# can.net
KiCad netlist of a schematic drawn in Altium Designer
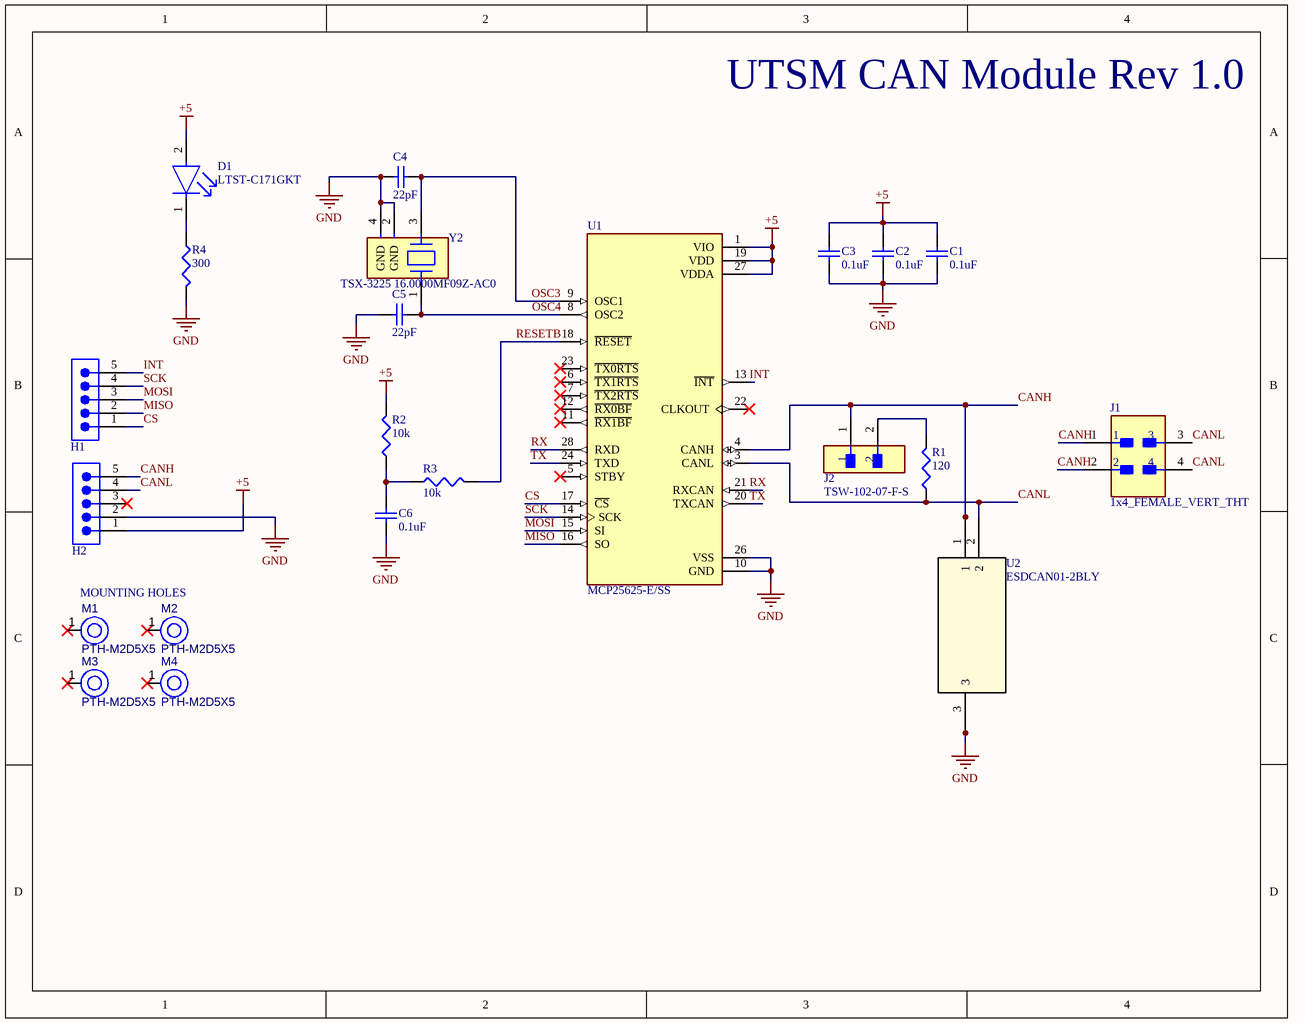
[diagram p0: can.SchDoc]

(export (version "E")
  (design (tool "Eeschema 10.0.6"))
  (components
    (comp (ref "C1")
      (value "0.1uF")
      (footprint "0603c")
      (description "0603 Capacitor")
      (fields (field (name "Comment") "Cap") (field (name "PUBLISHER") "Altium Limited"))
      (libsource (lib "Peripheral") (part "Cap"))
    )
    (comp (ref "C2")
      (value "0.1uF")
      (footprint "0603c")
      (description "SMD Capacitor")
      (fields (field (name "Comment") "Cap") (field (name "PUBLISHER") "Altium Limited"))
      (libsource (lib "can") (part "Cap"))
    )
    (comp (ref "C3")
      (value "0.1uF")
      (footprint "0603c")
      (description "SMD Capacitor")
      (fields (field (name "Comment") "Cap") (field (name "PUBLISHER") "Altium Limited"))
      (libsource (lib "can") (part "Cap"))
    )
    (comp (ref "C4")
      (value "22pF")
      (footprint "0603c")
      (description "0603 Capacitor")
      (fields (field (name "PUBLISHER") "Altium Limited"))
      (libsource (lib "can") (part "Cap"))
    )
    (comp (ref "C5")
      (value "22pF")
      (footprint "0603c")
      (description "SMD Capacitor")
      (fields (field (name "Comment") "Cap") (field (name "PUBLISHER") "Altium Limited"))
      (libsource (lib "can") (part "Cap"))
    )
    (comp (ref "C6")
      (value "0.1uF")
      (footprint "0603c")
      (description "SMD Capacitor")
      (fields (field (name "Comment") "Cap") (field (name "PUBLISHER") "Altium Limited"))
      (libsource (lib "can") (part "Cap"))
    )
    (comp (ref "D1")
      (value "LTST-C171GKT")
      (footprint "FP-LTST-C171GKT-MFG")
      (description "LED GREEN CLEAR CHIP SMD")
      (libsource (lib "Altium Content Vault") (part "8706943c75ba83719d021d2fdc84c58"))
    )
    (comp (ref "H1")
      (value "61300511121")
      (footprint "can:61300511121")
      (description "WR-PHD Pin Header, THT, Vertical, pitch 2.54mm, 1 Row, 5P")
      (fields (field (name "MANUFACTURER") "Wurth Elektronik"))
      (libsource (lib "can") (part "61300511121"))
    )
    (comp (ref "H2")
      (value "61300511121")
      (footprint "61300511121")
      (description "WR-PHD Pin Header, THT, Vertical, pitch 2.54mm, 1 Row, 5P")
      (fields (field (name "MANUFACTURER") "Wurth Elektronik"))
      (libsource (lib "can") (part "61300511121"))
    )
    (comp (ref "J1")
      (value "1x4_FEMALE_VERT_THT")
      (footprint "FP-0039281043-MFG")
      (description "CONN HEADER VERT 4POS 4.2MM. 0039281043")
      (fields (field (name "MANUFACTURER PART NUMBER") "0039281043") (field (name "MANUFACTURER") "Molex"))
      (libsource (lib "can") (part "1x4_FEMALE_POWER"))
    )
    (comp (ref "J2")
      (value "TSW-102-07-F-S")
      (footprint "FP-TSW-102-07-F-S-MFG")
      (description "CONN HEADER VERT 2POS 2.54MM")
      (libsource (lib "Altium Content Vault") (part "3bc925449376181038e59eaffc5286c"))
    )
    (comp (ref "M1")
      (value "PTH-M2D5X5")
      (footprint "PTH-M2D5X5")
      (description "M2 PTH (2.5mm), 5mm pad")
      (libsource (lib "can") (part "PTH-M2D5X5"))
    )
    (comp (ref "M2")
      (value "PTH-M2D5X5")
      (footprint "PTH-M2D5X5")
      (description "M2 PTH (2.5mm), 5mm pad")
      (libsource (lib "can") (part "PTH-M2D5X5"))
    )
    (comp (ref "M3")
      (value "PTH-M2D5X5")
      (footprint "PTH-M2D5X5")
      (description "M2 PTH (2.5mm), 5mm pad")
      (libsource (lib "can") (part "PTH-M2D5X5"))
    )
    (comp (ref "M4")
      (value "PTH-M2D5X5")
      (footprint "PTH-M2D5X5")
      (description "M2 PTH (2.5mm), 5mm pad")
      (libsource (lib "can") (part "PTH-M2D5X5"))
    )
    (comp (ref "R1")
      (value "120")
      (footprint "0603r")
      (description "SMD Resistor")
      (fields (field (name "Comment") "Res3") (field (name "PUBLISHER") "Altium Limited"))
      (libsource (lib "can") (part "Res3"))
    )
    (comp (ref "R2")
      (value "10k")
      (footprint "0603r")
      (description "SMD Resistor")
      (fields (field (name "Comment") "Res3") (field (name "PUBLISHER") "Altium Limited"))
      (libsource (lib "can") (part "Res3"))
    )
    (comp (ref "R3")
      (value "10k")
      (footprint "0603r")
      (description "SMD Resistor")
      (fields (field (name "Comment") "Res3") (field (name "PUBLISHER") "Altium Limited"))
      (libsource (lib "can") (part "Res3"))
    )
    (comp (ref "R4")
      (value "300")
      (footprint "0603r")
      (description "SMD Resistor")
      (fields (field (name "Comment") "Res3") (field (name "PUBLISHER") "Altium Limited"))
      (libsource (lib "can") (part "Res3"))
    )
    (comp (ref "U1")
      (value "MCP25625-E/SS")
      (footprint "SOP65P780X200-28N")
      (description "1/1 Transceiver CANbus 28-SSOP")
      (fields (field (name "MF") "Microchip"))
      (libsource (lib "can") (part "MCP25625-E/SS"))
    )
    (comp (ref "U2")
      (value "ESDCAN01-2BLY")
      (footprint "SOT_01-2BLY_STM")
      (fields (field (name "COPYRIGHT") "Copyright (C) 2023 Ultra Librarian. All rights reserved."))
      (libsource (lib "can") (part "ESDCAN01-2BLY"))
    )
    (comp (ref "Y2")
      (value "TSX-3225 16.0000MF09Z-AC0")
      (footprint "FP-TSX-3225-MFG")
      (description "CRYSTAL 16.0000MHZ 9PF SMD")
      (fields (field (name "TOLERANCE") "10ppm"))
      (libsource (lib "Altium Content Vault") (part "41079aabb0e87794b56622915be14ed"))
    )
  )
  (nets
    (net (code "1") (name "+5") (class "Default")
      (node (ref "C1") (pin "2") (pinfunction "2_2") (pintype "passive"))
      (node (ref "C2") (pin "2") (pinfunction "2_2") (pintype "passive"))
      (node (ref "C3") (pin "2") (pinfunction "2_2") (pintype "passive"))
      (node (ref "D1") (pin "2") (pinfunction "A_2") (pintype "passive"))
      (node (ref "H2") (pin "1") (pinfunction "1_1") (pintype "passive"))
      (node (ref "R2") (pin "2") (pinfunction "2_2") (pintype "passive"))
      (node (ref "U1") (pin "1") (pinfunction "VIO_1") (pintype "power_in"))
      (node (ref "U1") (pin "19") (pinfunction "VDD_19") (pintype "power_in"))
      (node (ref "U1") (pin "27") (pinfunction "VDDA_27") (pintype "power_in"))
    )
    (net (code "3") (name "/CANH") (class "Default")
      (node (ref "H2") (pin "5") (pinfunction "5_5") (pintype "passive"))
      (node (ref "J1") (pin "1") (pinfunction "1_1") (pintype "passive"))
      (node (ref "J1") (pin "2") (pinfunction "2_2") (pintype "passive"))
      (node (ref "J2") (pin "1") (pinfunction "1_1") (pintype "passive"))
      (node (ref "U1") (pin "4") (pinfunction "CANH_4") (pintype "bidirectional"))
      (node (ref "U2") (pin "1") (pinfunction "1_1") (pintype "passive"))
    )
    (net (code "4") (name "/CANL") (class "Default")
      (node (ref "H2") (pin "4") (pinfunction "4_4") (pintype "passive"))
      (node (ref "J1") (pin "3") (pinfunction "3_3") (pintype "passive"))
      (node (ref "J1") (pin "4") (pinfunction "4_4") (pintype "passive"))
      (node (ref "R1") (pin "1") (pinfunction "1_1") (pintype "passive"))
      (node (ref "U1") (pin "3") (pinfunction "CANL_3") (pintype "bidirectional"))
      (node (ref "U2") (pin "2") (pinfunction "2_2") (pintype "passive"))
    )
    (net (code "5") (name "/CS") (class "Default")
      (node (ref "H1") (pin "1") (pinfunction "1_1") (pintype "passive"))
      (node (ref "U1") (pin "17") (pinfunction "~{CS}_17") (pintype "input"))
    )
    (net (code "6") (name "/INT") (class "Default")
      (node (ref "H1") (pin "5") (pinfunction "5_5") (pintype "passive"))
      (node (ref "U1") (pin "13") (pinfunction "~{INT}_13") (pintype "output"))
    )
    (net (code "7") (name "/MISO") (class "Default")
      (node (ref "H1") (pin "2") (pinfunction "2_2") (pintype "passive"))
      (node (ref "U1") (pin "16") (pinfunction "SO_16") (pintype "output"))
    )
    (net (code "8") (name "/MOSI") (class "Default")
      (node (ref "H1") (pin "3") (pinfunction "3_3") (pintype "passive"))
      (node (ref "U1") (pin "15") (pinfunction "SI_15") (pintype "input"))
    )
    (net (code "9") (name "/OSC3") (class "Default")
      (node (ref "C4") (pin "2") (pinfunction "2_2") (pintype "passive"))
      (node (ref "U1") (pin "9") (pinfunction "OSC1_9") (pintype "input"))
      (node (ref "Y2") (pin "3") (pinfunction "3_3") (pintype "passive"))
    )
    (net (code "10") (name "/OSC4") (class "Default")
      (node (ref "C5") (pin "2") (pinfunction "2_2") (pintype "passive"))
      (node (ref "U1") (pin "8") (pinfunction "OSC2_8") (pintype "output"))
      (node (ref "Y2") (pin "1") (pinfunction "1_1") (pintype "passive"))
    )
    (net (code "11") (name "/RESETB") (class "Default")
      (node (ref "R3") (pin "2") (pinfunction "2_2") (pintype "passive"))
      (node (ref "U1") (pin "18") (pinfunction "~{RESET}_18") (pintype "input"))
    )
    (net (code "12") (name "/RX") (class "Default")
      (node (ref "U1") (pin "21") (pinfunction "RXCAN_21") (pintype "input"))
      (node (ref "U1") (pin "28") (pinfunction "RXD_28") (pintype "output"))
    )
    (net (code "13") (name "/SCK") (class "Default")
      (node (ref "H1") (pin "4") (pinfunction "4_4") (pintype "passive"))
      (node (ref "U1") (pin "14") (pinfunction "SCK_14") (pintype "input"))
    )
    (net (code "14") (name "/TX") (class "Default")
      (node (ref "U1") (pin "20") (pinfunction "TXCAN_20") (pintype "output"))
      (node (ref "U1") (pin "24") (pinfunction "TXD_24") (pintype "input"))
    )
    (net (code "15") (name "GND") (class "Default")
      (node (ref "C1") (pin "1") (pinfunction "1_1") (pintype "passive"))
      (node (ref "C2") (pin "1") (pinfunction "1_1") (pintype "passive"))
      (node (ref "C3") (pin "1") (pinfunction "1_1") (pintype "passive"))
      (node (ref "C4") (pin "1") (pinfunction "1_1") (pintype "passive"))
      (node (ref "C5") (pin "1") (pinfunction "1_1") (pintype "passive"))
      (node (ref "C6") (pin "1") (pinfunction "1_1") (pintype "passive"))
      (node (ref "H2") (pin "2") (pinfunction "2_2") (pintype "passive"))
      (node (ref "R4") (pin "2") (pinfunction "2_2") (pintype "passive"))
      (node (ref "U1") (pin "10") (pinfunction "GND_10") (pintype "power_in"))
      (node (ref "U1") (pin "26") (pinfunction "VSS_26") (pintype "power_in"))
      (node (ref "U2") (pin "3") (pinfunction "3_3") (pintype "passive"))
      (node (ref "Y2") (pin "2") (pinfunction "GND_2") (pintype "power_in"))
      (node (ref "Y2") (pin "4") (pinfunction "GND_4") (pintype "power_in"))
    )
    (net (code "16") (name "Net-(C6-Pad2)") (class "Default")
      (node (ref "C6") (pin "2") (pinfunction "2_2") (pintype "passive"))
      (node (ref "R2") (pin "1") (pinfunction "1_1") (pintype "passive"))
      (node (ref "R3") (pin "1") (pinfunction "1_1") (pintype "passive"))
    )
    (net (code "17") (name "Net-(D1-C)") (class "Default")
      (node (ref "D1") (pin "1") (pinfunction "C_1") (pintype "passive"))
      (node (ref "R4") (pin "1") (pinfunction "1_1") (pintype "passive"))
    )
    (net (code "18") (name "Net-(J2-Pad2)") (class "Default")
      (node (ref "J2") (pin "2") (pinfunction "2_2") (pintype "passive"))
      (node (ref "R1") (pin "2") (pinfunction "2_2") (pintype "passive"))
    )
    (net (code "19") (name "unconnected-(H2-Pad3)") (class "Default")
      (node (ref "H2") (pin "3") (pinfunction "3_3") (pintype "passive+no_connect"))
    )
    (net (code "20") (name "unconnected-(M1-H1-Pad1)") (class "Default")
      (node (ref "M1") (pin "1") (pinfunction "H1_1") (pintype "passive+no_connect"))
    )
    (net (code "21") (name "unconnected-(M2-H1-Pad1)") (class "Default")
      (node (ref "M2") (pin "1") (pinfunction "H1_1") (pintype "passive+no_connect"))
    )
    (net (code "22") (name "unconnected-(M3-H1-Pad1)") (class "Default")
      (node (ref "M3") (pin "1") (pinfunction "H1_1") (pintype "passive+no_connect"))
    )
    (net (code "23") (name "unconnected-(M4-H1-Pad1)") (class "Default")
      (node (ref "M4") (pin "1") (pinfunction "H1_1") (pintype "passive+no_connect"))
    )
    (net (code "24") (name "unconnected-(U1-CLKOUT-Pad22)") (class "Default")
      (node (ref "U1") (pin "22") (pinfunction "CLKOUT_22") (pintype "output+no_connect"))
    )
    (net (code "25") (name "unconnected-(U1-STBY-Pad5)") (class "Default")
      (node (ref "U1") (pin "5") (pinfunction "STBY_5") (pintype "input+no_connect"))
    )
    (net (code "26") (name "unconnected-(U1-~{RX0BF}-Pad12)") (class "Default")
      (node (ref "U1") (pin "12") (pinfunction "~{RX0BF}_12") (pintype "output+no_connect"))
    )
    (net (code "27") (name "unconnected-(U1-~{RX1BF}-Pad11)") (class "Default")
      (node (ref "U1") (pin "11") (pinfunction "~{RX1BF}_11") (pintype "output+no_connect"))
    )
    (net (code "28") (name "unconnected-(U1-~{TX0RTS}-Pad23)") (class "Default")
      (node (ref "U1") (pin "23") (pinfunction "~{TX0RTS}_23") (pintype "input+no_connect"))
    )
    (net (code "29") (name "unconnected-(U1-~{TX1RTS}-Pad6)") (class "Default")
      (node (ref "U1") (pin "6") (pinfunction "~{TX1RTS}_6") (pintype "input+no_connect"))
    )
    (net (code "30") (name "unconnected-(U1-~{TX2RTS}-Pad7)") (class "Default")
      (node (ref "U1") (pin "7") (pinfunction "~{TX2RTS}_7") (pintype "input+no_connect"))
    )
  )
)
